# FRAM_memory.net
KiCad netlist of a schematic drawn in Altium Designer
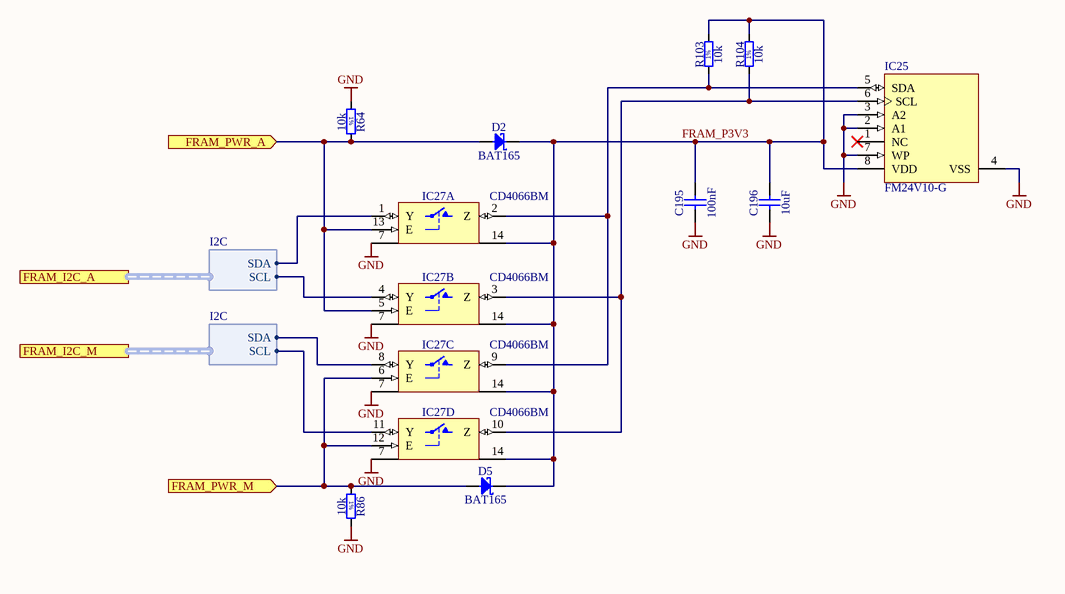
[diagram p0: FRAM_memory.SchDoc]

(export (version "E")
  (design (tool "Eeschema 10.0.6"))
  (components
    (comp (ref "C195")
      (value "100nF")
      (footprint "CAPC1005X55N")
      (description "Non-polarised capacitor")
      (fields
        (field (name "PART NUMBER") "CC0402_100NF_25V_10%_X7R_YUDEN_TMK105B7104KVHF")
        (field (name "VOLTAGE") "25V")
        (field (name "AUTHOR") "CERN DEM JLC")
      )
      (libsource (lib "Capacitors") (part "Capacitor - non polarized"))
    )
    (comp (ref "C196")
      (value "10uF")
      (footprint "CAPC1608X80N")
      (description "Non-polarised capacitor")
      (fields
        (field (name "PART NUMBER") "CC0603_10UF_16V_20%_X5R")
        (field (name "VOLTAGE") "16V")
        (field (name "AUTHOR") "CERN DEM MR")
      )
      (libsource (lib "Capacitors") (part "Capacitor - non polarized"))
    )
    (comp (ref "D2")
      (value "BAT165")
      (footprint "SOD2512X110N")
      (description "Schottky Diode")
      (fields
        (field (name "VOLTAGE") "40V")
        (field (name "POWER") "750mA")
        (field (name "AUTHOR") "CERN DEM JLC")
      )
      (libsource (lib "ICs And Semiconductors") (part "Diode Schottky"))
    )
    (comp (ref "D5")
      (value "BAT165")
      (footprint "SOD2512X110N")
      (description "Schottky Diode")
      (fields
        (field (name "VOLTAGE") "40V")
        (field (name "POWER") "750mA")
        (field (name "AUTHOR") "CERN DEM JLC")
      )
      (libsource (lib "ICs And Semiconductors") (part "Diode Schottky"))
    )
    (comp (ref "IC25")
      (value "FM24V10-G")
      (footprint "SOIC127P600X175-8N")
      (fields (field (name "MANUFACTURER") "Cypress"))
      (libsource (lib "LIBRARY_SCH") (part "MEM_FM24V10-G"))
    )
    (comp (ref "IC27")
      (value "CD4066BM")
      (footprint "SOIC127P600X175-14N")
      (fields (field (name "MANUFACTURER") "TEXAS INSTRUMENTS") (field (name "AUTHOR") "CERN DEM MR"))
      (libsource (lib "ICs And Semiconductors") (part "4066_a"))
    )
    (comp (ref "R64")
      (value "10k")
      (footprint "RESC1005X40N")
      (description "Resistor - 1%")
      (fields
        (field (name "PART NUMBER") "R0402_10K_1%_0.0625W_100PPM")
        (field (name "POWER") "0.0625W")
        (field (name "AUTHOR") "CERN DEM JLC")
      )
      (libsource (lib "Resistors") (part "Resistor - 1%"))
    )
    (comp (ref "R86")
      (value "10k")
      (footprint "RESC1005X40N")
      (description "Resistor - 1%")
      (fields
        (field (name "PART NUMBER") "R0402_10K_1%_0.0625W_100PPM")
        (field (name "POWER") "0.0625W")
        (field (name "AUTHOR") "CERN DEM JLC")
      )
      (libsource (lib "Resistors") (part "Resistor - 1%"))
    )
    (comp (ref "R103")
      (value "10k")
      (footprint "RESC1005X40N")
      (description "Resistor - 1%")
      (fields
        (field (name "PART NUMBER") "R0402_10K_1%_0.0625W_100PPM")
        (field (name "POWER") "0.0625W")
        (field (name "AUTHOR") "CERN DEM JLC")
      )
      (libsource (lib "Resistors") (part "Resistor - 1%"))
    )
    (comp (ref "R104")
      (value "10k")
      (footprint "RESC1005X40N")
      (description "Resistor - 1%")
      (fields
        (field (name "PART NUMBER") "R0402_10K_1%_0.0625W_100PPM")
        (field (name "POWER") "0.0625W")
        (field (name "AUTHOR") "CERN DEM JLC")
      )
      (libsource (lib "Resistors") (part "Resistor - 1%"))
    )
  )
  (nets
    (net (code "2") (name "/FRAM_PWR_A") (class "Default")
      (node (ref "D2") (pin "2") (pinfunction "A_2") (pintype "passive"))
      (node (ref "IC27") (pin "13") (pinfunction "E_13") (pintype "input"))
      (node (ref "IC27") (pin "5") (pinfunction "E_5") (pintype "input"))
      (node (ref "R64") (pin "2") (pinfunction "2_2") (pintype "passive"))
    )
    (net (code "3") (name "/FRAM_PWR_M") (class "Default")
      (node (ref "D5") (pin "2") (pinfunction "A_2") (pintype "passive"))
      (node (ref "IC27") (pin "12") (pinfunction "E_12") (pintype "input"))
      (node (ref "IC27") (pin "6") (pinfunction "E_6") (pintype "input"))
      (node (ref "R86") (pin "1") (pinfunction "1_1") (pintype "passive"))
    )
    (net (code "5") (name "GND") (class "Default")
      (node (ref "C195") (pin "1") (pinfunction "1_1") (pintype "passive"))
      (node (ref "C196") (pin "1") (pinfunction "1_1") (pintype "passive"))
      (node (ref "IC25") (pin "2") (pinfunction "A1_2") (pintype "input"))
      (node (ref "IC25") (pin "3") (pinfunction "A2_3") (pintype "input"))
      (node (ref "IC25") (pin "4") (pinfunction "VSS_4") (pintype "power_in"))
      (node (ref "IC25") (pin "7") (pinfunction "WP_7") (pintype "input"))
      (node (ref "IC27") (pin "7") (pinfunction "VSS_7") (pintype "power_in"))
      (node (ref "R64") (pin "1") (pinfunction "1_1") (pintype "passive"))
      (node (ref "R86") (pin "2") (pinfunction "2_2") (pintype "passive"))
    )
    (net (code "6") (name "Net-(IC25-SCL)") (class "Default")
      (node (ref "IC25") (pin "6") (pinfunction "SCL_6") (pintype "input"))
      (node (ref "IC27") (pin "10") (pinfunction "Z_10") (pintype "bidirectional"))
      (node (ref "IC27") (pin "3") (pinfunction "Z_3") (pintype "bidirectional"))
      (node (ref "R104") (pin "1") (pinfunction "1_1") (pintype "passive"))
    )
    (net (code "7") (name "Net-(IC25-SDA)") (class "Default")
      (node (ref "IC25") (pin "5") (pinfunction "SDA_5") (pintype "bidirectional"))
      (node (ref "IC27") (pin "2") (pinfunction "Z_2") (pintype "bidirectional"))
      (node (ref "IC27") (pin "9") (pinfunction "Z_9") (pintype "bidirectional"))
      (node (ref "R103") (pin "1") (pinfunction "1_1") (pintype "passive"))
    )
    (net (code "8") (name "VDD") (class "Default")
      (node (ref "C195") (pin "2") (pinfunction "2_2") (pintype "passive"))
      (node (ref "C196") (pin "2") (pinfunction "2_2") (pintype "passive"))
      (node (ref "D2") (pin "1") (pinfunction "C_1") (pintype "passive"))
      (node (ref "D5") (pin "1") (pinfunction "C_1") (pintype "passive"))
      (node (ref "IC25") (pin "8") (pinfunction "VDD_8") (pintype "power_in"))
      (node (ref "IC27") (pin "14") (pinfunction "VDD_14") (pintype "power_in"))
      (node (ref "R103") (pin "2") (pinfunction "2_2") (pintype "passive"))
      (node (ref "R104") (pin "2") (pinfunction "2_2") (pintype "passive"))
    )
    (net (code "9") (name "unconnected-(IC25-NC-Pad1)") (class "Default")
      (node (ref "IC25") (pin "1") (pinfunction "NC_1") (pintype "passive+no_connect"))
    )
    (net (code "10") (name "unconnected-(IC27A-Y-Pad1)") (class "Default")
      (node (ref "IC27") (pin "1") (pinfunction "Y_1") (pintype "bidirectional"))
    )
    (net (code "11") (name "unconnected-(IC27B-Y-Pad4)") (class "Default")
      (node (ref "IC27") (pin "4") (pinfunction "Y_4") (pintype "bidirectional"))
    )
    (net (code "12") (name "unconnected-(IC27C-Y-Pad8)") (class "Default")
      (node (ref "IC27") (pin "8") (pinfunction "Y_8") (pintype "bidirectional"))
    )
    (net (code "13") (name "unconnected-(IC27D-Y-Pad11)") (class "Default")
      (node (ref "IC27") (pin "11") (pinfunction "Y_11") (pintype "bidirectional"))
    )
  )
)
